# Analogue.net
KiCad netlist of a schematic drawn in Altium Designer
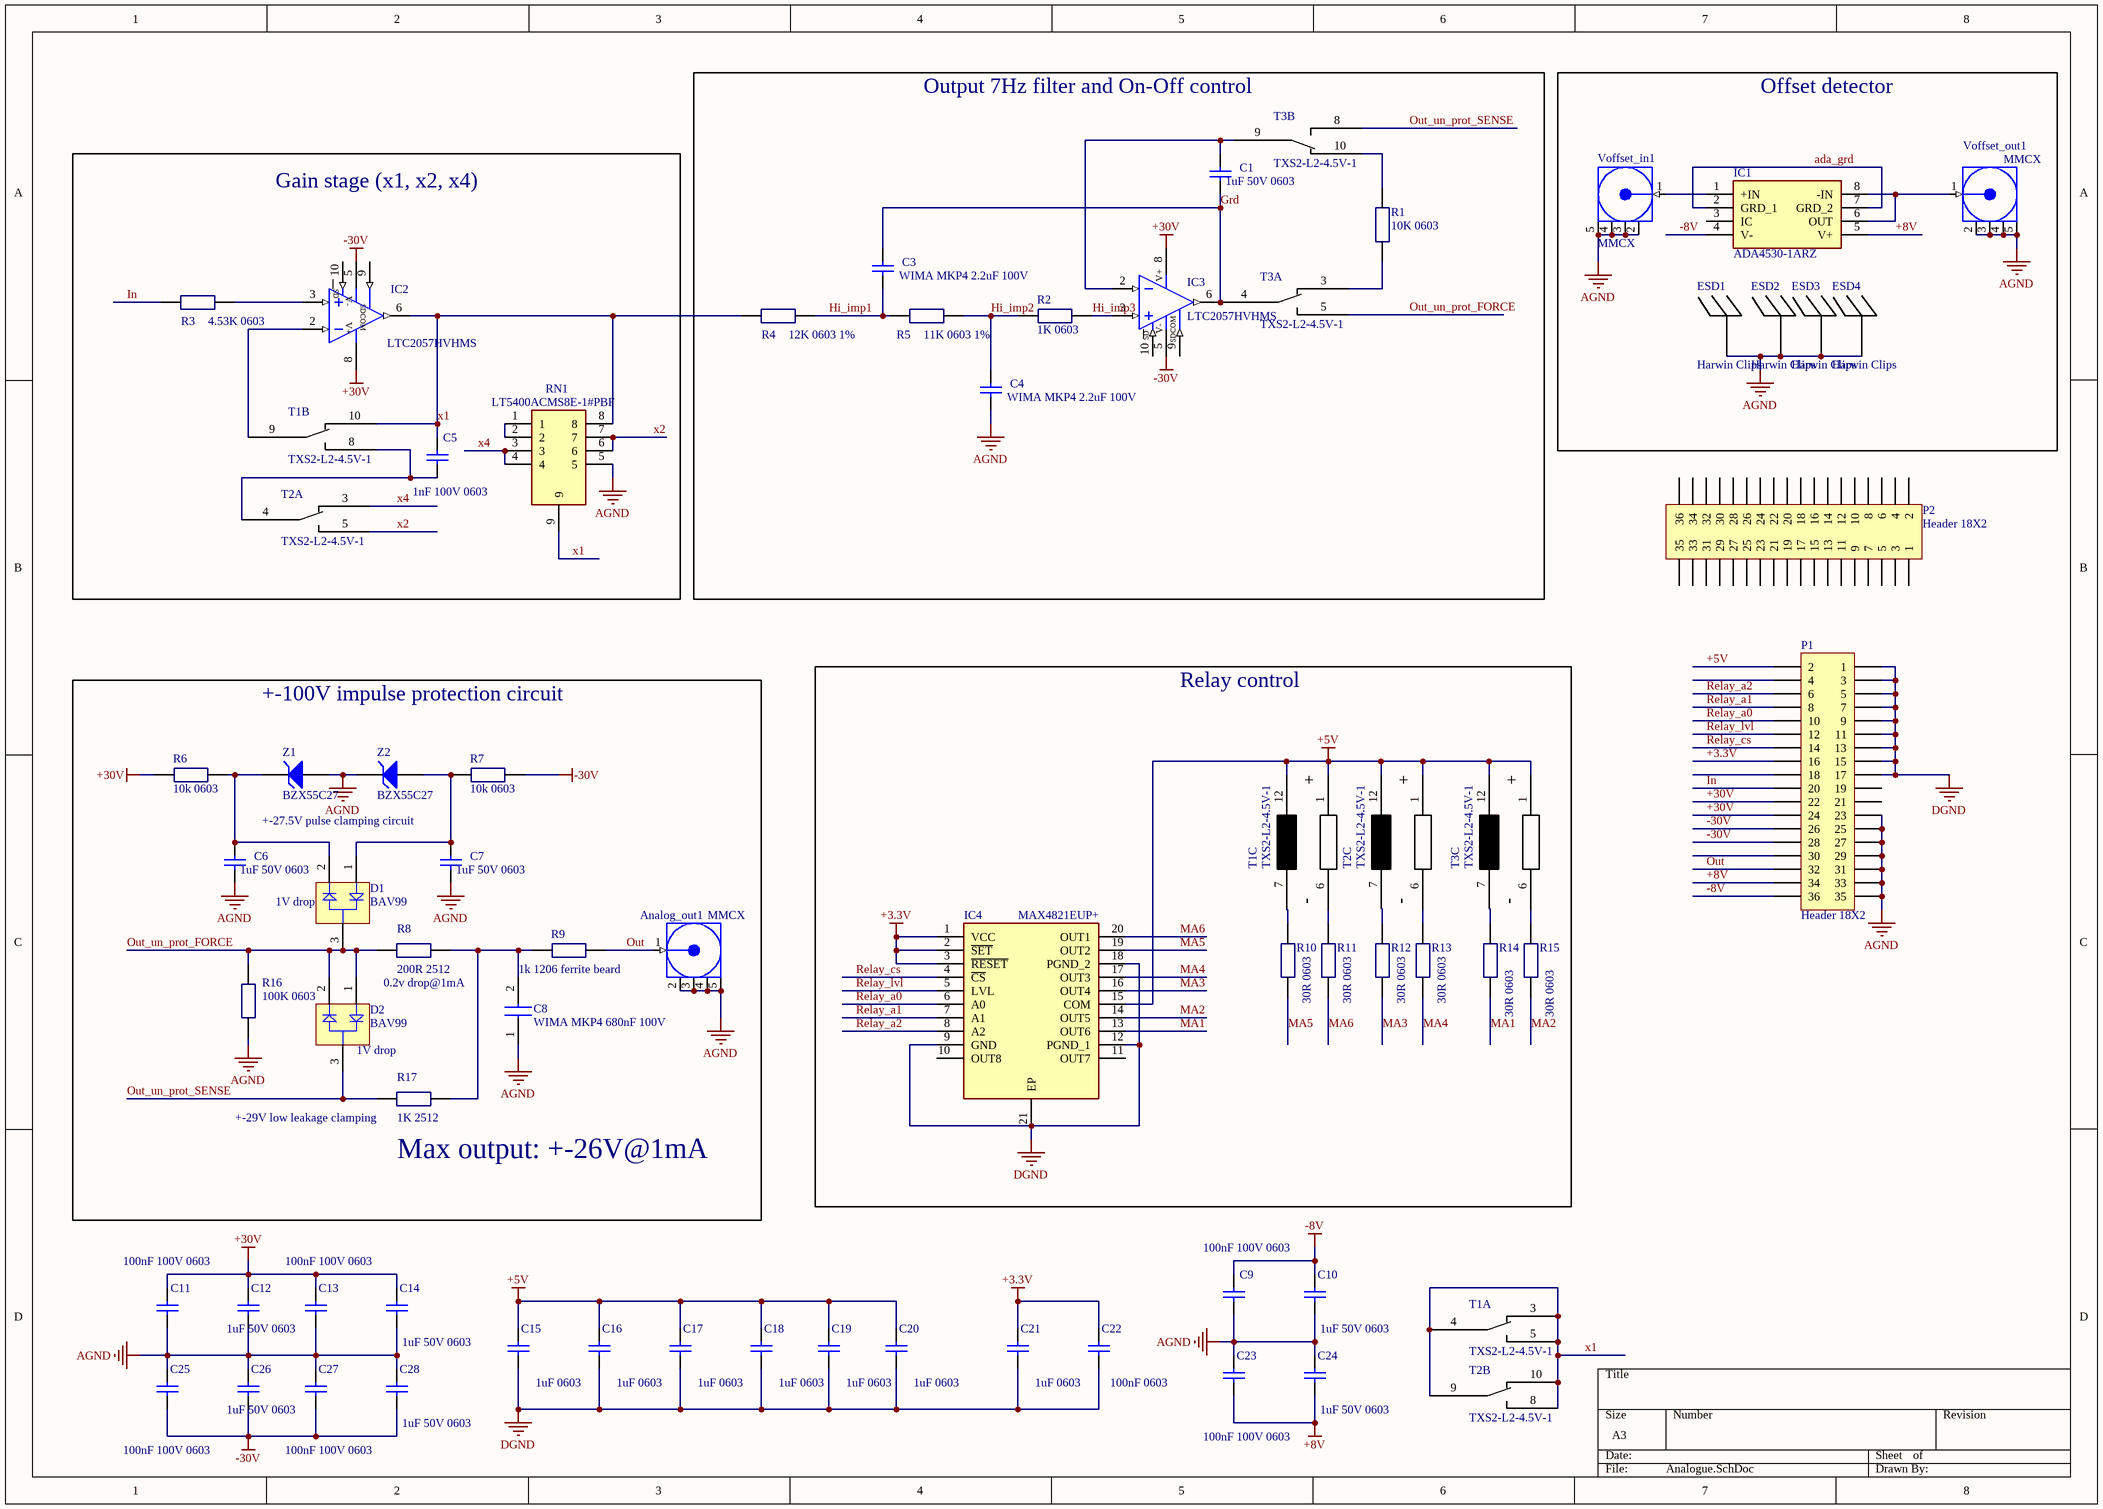
[diagram p0: Analogue.SchDoc]

(export (version "E")
  (design (tool "Eeschema 10.0.6"))
  (components
    (comp (ref "Analog_out1")
      (value "MMCX")
      (footprint "MMCX2.54-V5")
      (description "RF Coaxial PCB Connector, MMCX; Thru-Hole, Vertical Mount Plug,  50 Ohm Impedance")
      (fields (field (name "PUBLISHER") "Altium Limited"))
      (libsource (lib "Miscellaneous Connectors") (part "COAX-M"))
    )
    (comp (ref "C1")
      (value "1uF 50V 0603")
      (footprint "CAP 0603")
      (description "Non-polarised capacitor")
      (fields
        (field (name "PART NUMBER") "CC1206_1UF_25V_10%_X7R")
        (field (name "VOLTAGE") "25V")
        (field (name "AUTHOR") "CERN DEM JLC")
      )
      (libsource (lib "Capacitors") (part "Capacitor - non polarized"))
    )
    (comp (ref "C3")
      (value "WIMA MKP4 2.2uF 100V")
      (footprint "90g WIMA MKP4 2.2uF 100V")
      (description "Non-polarised capacitor")
      (fields
        (field (name "PART NUMBER") "CC1206_1UF_25V_10%_X7R")
        (field (name "VOLTAGE") "25V")
        (field (name "AUTHOR") "CERN DEM JLC")
      )
      (libsource (lib "Capacitors") (part "Capacitor - non polarized"))
    )
    (comp (ref "C4")
      (value "WIMA MKP4 2.2uF 100V")
      (footprint "90g WIMA MKP4 2.2uF 100V")
      (description "Non-polarised capacitor")
      (fields
        (field (name "PART NUMBER") "CC1206_1UF_25V_10%_X7R")
        (field (name "VOLTAGE") "25V")
        (field (name "AUTHOR") "CERN DEM JLC")
      )
      (libsource (lib "Capacitors") (part "Capacitor - non polarized"))
    )
    (comp (ref "C5")
      (value "1nF 100V 0603")
      (footprint "CAP 0603")
      (description "Non-polarised capacitor")
      (fields
        (field (name "PART NUMBER") "CC1206_1UF_25V_10%_X7R")
        (field (name "VOLTAGE") "25V")
        (field (name "AUTHOR") "CERN DEM JLC")
      )
      (libsource (lib "Capacitors") (part "Capacitor - non polarized"))
    )
    (comp (ref "C6")
      (value "1uF 50V 0603")
      (footprint "CAP 0603")
      (description "Non-polarised capacitor")
      (fields
        (field (name "PART NUMBER") "CC1206_1UF_25V_10%_X7R")
        (field (name "VOLTAGE") "25V")
        (field (name "AUTHOR") "CERN DEM JLC")
      )
      (libsource (lib "Capacitors") (part "Capacitor - non polarized"))
    )
    (comp (ref "C7")
      (value "1uF 50V 0603")
      (footprint "CAP 0603")
      (description "Non-polarised capacitor")
      (fields
        (field (name "PART NUMBER") "CC1206_1UF_25V_10%_X7R")
        (field (name "VOLTAGE") "25V")
        (field (name "AUTHOR") "CERN DEM JLC")
      )
      (libsource (lib "Capacitors") (part "Capacitor - non polarized"))
    )
    (comp (ref "C8")
      (value "WIMA MKP4 680nF 100V")
      (footprint "SamacSys:MKP4F036804F00KSSD")
      (description "Capacitor")
      (fields
        (field (name "MANUFACTURER_PART_NUMBER") "MKP4F036804F00KSSD")
        (field (name "MOUSER PART NUMBER") "505-MKP4F036804F00KS")
      )
      (libsource (lib "SamacSys") (part "MKP4F036804F00KSSD"))
    )
    (comp (ref "C9")
      (value "100nF 100V 0603")
      (footprint "CAP 0603")
      (description "Non-polarised capacitor")
      (fields
        (field (name "PART NUMBER") "CC1206_1UF_25V_10%_X7R")
        (field (name "VOLTAGE") "25V")
        (field (name "AUTHOR") "CERN DEM JLC")
      )
      (libsource (lib "Capacitors") (part "Capacitor - non polarized"))
    )
    (comp (ref "C10")
      (value "1uF 50V 0603")
      (footprint "CAP 0603")
      (description "Non-polarised capacitor")
      (fields
        (field (name "PART NUMBER") "CC1206_1UF_25V_10%_X7R")
        (field (name "VOLTAGE") "25V")
        (field (name "AUTHOR") "CERN DEM JLC")
      )
      (libsource (lib "Capacitors") (part "Capacitor - non polarized"))
    )
    (comp (ref "C11")
      (value "100nF 100V 0603")
      (footprint "CAP 0603")
      (description "Non-polarised capacitor")
      (fields
        (field (name "PART NUMBER") "CC1206_1UF_25V_10%_X7R")
        (field (name "VOLTAGE") "25V")
        (field (name "AUTHOR") "CERN DEM JLC")
      )
      (libsource (lib "Capacitors") (part "Capacitor - non polarized"))
    )
    (comp (ref "C12")
      (value "1uF 50V 0603")
      (footprint "CAP 0603")
      (description "Non-polarised capacitor")
      (fields
        (field (name "PART NUMBER") "CC1206_1UF_25V_10%_X7R")
        (field (name "VOLTAGE") "25V")
        (field (name "AUTHOR") "CERN DEM JLC")
      )
      (libsource (lib "Capacitors") (part "Capacitor - non polarized"))
    )
    (comp (ref "C13")
      (value "100nF 100V 0603")
      (footprint "CAP 0603")
      (description "Non-polarised capacitor")
      (fields
        (field (name "PART NUMBER") "CC1206_1UF_25V_10%_X7R")
        (field (name "VOLTAGE") "25V")
        (field (name "AUTHOR") "CERN DEM JLC")
      )
      (libsource (lib "Capacitors") (part "Capacitor - non polarized"))
    )
    (comp (ref "C14")
      (value "1uF 50V 0603")
      (footprint "CAP 0603")
      (description "Non-polarised capacitor")
      (fields
        (field (name "PART NUMBER") "CC1206_1UF_25V_10%_X7R")
        (field (name "VOLTAGE") "25V")
        (field (name "AUTHOR") "CERN DEM JLC")
      )
      (libsource (lib "Capacitors") (part "Capacitor - non polarized"))
    )
    (comp (ref "C15")
      (value "1uF 0603")
      (footprint "CAP 0603")
      (description "Non-polarised capacitor")
      (fields
        (field (name "PART NUMBER") "CC1206_1UF_25V_10%_X7R")
        (field (name "VOLTAGE") "25V")
        (field (name "AUTHOR") "CERN DEM JLC")
      )
      (libsource (lib "Capacitors") (part "Capacitor - non polarized"))
    )
    (comp (ref "C16")
      (value "1uF 0603")
      (footprint "CAP 0603")
      (description "Non-polarised capacitor")
      (fields
        (field (name "PART NUMBER") "CC1206_1UF_25V_10%_X7R")
        (field (name "VOLTAGE") "25V")
        (field (name "AUTHOR") "CERN DEM JLC")
      )
      (libsource (lib "Capacitors") (part "Capacitor - non polarized"))
    )
    (comp (ref "C17")
      (value "1uF 0603")
      (footprint "CAP 0603")
      (description "Non-polarised capacitor")
      (fields
        (field (name "PART NUMBER") "CC1206_1UF_25V_10%_X7R")
        (field (name "VOLTAGE") "25V")
        (field (name "AUTHOR") "CERN DEM JLC")
      )
      (libsource (lib "Capacitors") (part "Capacitor - non polarized"))
    )
    (comp (ref "C18")
      (value "1uF 0603")
      (footprint "CAP 0603")
      (description "Non-polarised capacitor")
      (fields
        (field (name "PART NUMBER") "CC1206_1UF_25V_10%_X7R")
        (field (name "VOLTAGE") "25V")
        (field (name "AUTHOR") "CERN DEM JLC")
      )
      (libsource (lib "Capacitors") (part "Capacitor - non polarized"))
    )
    (comp (ref "C19")
      (value "1uF 0603")
      (footprint "CAP 0603")
      (description "Non-polarised capacitor")
      (fields
        (field (name "PART NUMBER") "CC1206_1UF_25V_10%_X7R")
        (field (name "VOLTAGE") "25V")
        (field (name "AUTHOR") "CERN DEM JLC")
      )
      (libsource (lib "Capacitors") (part "Capacitor - non polarized"))
    )
    (comp (ref "C20")
      (value "1uF 0603")
      (footprint "CAP 0603")
      (description "Non-polarised capacitor")
      (fields
        (field (name "PART NUMBER") "CC1206_1UF_25V_10%_X7R")
        (field (name "VOLTAGE") "25V")
        (field (name "AUTHOR") "CERN DEM JLC")
      )
      (libsource (lib "Capacitors") (part "Capacitor - non polarized"))
    )
    (comp (ref "C21")
      (value "1uF 0603")
      (footprint "CAP 0603")
      (description "Non-polarised capacitor")
      (fields
        (field (name "PART NUMBER") "CC1206_1UF_25V_10%_X7R")
        (field (name "VOLTAGE") "25V")
        (field (name "AUTHOR") "CERN DEM JLC")
      )
      (libsource (lib "Capacitors") (part "Capacitor - non polarized"))
    )
    (comp (ref "C22")
      (value "100nF 0603")
      (footprint "CAP 0603")
      (description "Non-polarised capacitor")
      (fields
        (field (name "PART NUMBER") "CC1206_1UF_25V_10%_X7R")
        (field (name "VOLTAGE") "25V")
        (field (name "AUTHOR") "CERN DEM JLC")
      )
      (libsource (lib "Capacitors") (part "Capacitor - non polarized"))
    )
    (comp (ref "C23")
      (value "100nF 100V 0603")
      (footprint "CAP 0603")
      (description "Non-polarised capacitor")
      (fields
        (field (name "PART NUMBER") "CC1206_1UF_25V_10%_X7R")
        (field (name "VOLTAGE") "25V")
        (field (name "AUTHOR") "CERN DEM JLC")
      )
      (libsource (lib "Capacitors") (part "Capacitor - non polarized"))
    )
    (comp (ref "C24")
      (value "1uF 50V 0603")
      (footprint "CAP 0603")
      (description "Non-polarised capacitor")
      (fields
        (field (name "PART NUMBER") "CC1206_1UF_25V_10%_X7R")
        (field (name "VOLTAGE") "25V")
        (field (name "AUTHOR") "CERN DEM JLC")
      )
      (libsource (lib "Capacitors") (part "Capacitor - non polarized"))
    )
    (comp (ref "C25")
      (value "100nF 100V 0603")
      (footprint "CAP 0603")
      (description "Non-polarised capacitor")
      (fields
        (field (name "PART NUMBER") "CC1206_1UF_25V_10%_X7R")
        (field (name "VOLTAGE") "25V")
        (field (name "AUTHOR") "CERN DEM JLC")
      )
      (libsource (lib "Capacitors") (part "Capacitor - non polarized"))
    )
    (comp (ref "C26")
      (value "1uF 50V 0603")
      (footprint "CAP 0603")
      (description "Non-polarised capacitor")
      (fields
        (field (name "PART NUMBER") "CC1206_1UF_25V_10%_X7R")
        (field (name "VOLTAGE") "25V")
        (field (name "AUTHOR") "CERN DEM JLC")
      )
      (libsource (lib "Capacitors") (part "Capacitor - non polarized"))
    )
    (comp (ref "C27")
      (value "100nF 100V 0603")
      (footprint "CAP 0603")
      (description "Non-polarised capacitor")
      (fields
        (field (name "PART NUMBER") "CC1206_1UF_25V_10%_X7R")
        (field (name "VOLTAGE") "25V")
        (field (name "AUTHOR") "CERN DEM JLC")
      )
      (libsource (lib "Capacitors") (part "Capacitor - non polarized"))
    )
    (comp (ref "C28")
      (value "1uF 50V 0603")
      (footprint "CAP 0603")
      (description "Non-polarised capacitor")
      (fields
        (field (name "PART NUMBER") "CC1206_1UF_25V_10%_X7R")
        (field (name "VOLTAGE") "25V")
        (field (name "AUTHOR") "CERN DEM JLC")
      )
      (libsource (lib "Capacitors") (part "Capacitor - non polarized"))
    )
    (comp (ref "D1")
      (value "BAV99")
      (footprint "INF-SOT23_N")
      (description "Silicon Switching Diode, SOT23, Reel, Green")
      (fields (field (name "MANUFACTURER") "Infineon"))
      (libsource (lib "Infineon_Transistor_&_Diode") (part "BAV99"))
    )
    (comp (ref "D2")
      (value "BAV99")
      (footprint "INF-SOT23_N")
      (description "Silicon Switching Diode, SOT23, Reel, Green")
      (fields (field (name "MANUFACTURER") "Infineon"))
      (libsource (lib "Infineon_Transistor_&_Diode") (part "BAV99"))
    )
    (comp (ref "ESD1")
      (value "Harwin Clips")
      (footprint "HARWIN - S0981-46R - CLIP")
      (libsource (lib "My SCH library") (part "Harwin Clips"))
    )
    (comp (ref "ESD2")
      (value "Harwin Clips")
      (footprint "HARWIN - S0981-46R - CLIP")
      (libsource (lib "My SCH library") (part "Harwin Clips"))
    )
    (comp (ref "ESD3")
      (value "Harwin Clips")
      (footprint "HARWIN - S0981-46R - CLIP")
      (libsource (lib "My SCH library") (part "Harwin Clips"))
    )
    (comp (ref "ESD4")
      (value "Harwin Clips")
      (footprint "HARWIN - S0981-46R - CLIP")
      (libsource (lib "My SCH library") (part "Harwin Clips"))
    )
    (comp (ref "IC1")
      (value "ADA4530-1ARZ")
      (footprint "SamacSys:SOIC127P600X175-8N")
      (description "Integrated Circuit")
      (fields (field (name "MOUSER PART NUMBER") "584-ADA4530-1ARZ"))
      (libsource (lib "*") (part "ADA4530-1ARZ"))
    )
    (comp (ref "IC2")
      (value "LTC2057HVHMS")
      (footprint "LT-MS-10_M")
      (description "High Voltage, Low Noise, Zero-Drift Operational  Amplifier")
      (libsource (lib "Operational Amplifiers") (part "LTC2057xHMS"))
    )
    (comp (ref "IC3")
      (value "LTC2057HVHMS")
      (footprint "LT-MS-10_M")
      (description "High Voltage, Low Noise, Zero-Drift Operational  Amplifier")
      (libsource (lib "Operational Amplifiers") (part "LTC2057xHMS"))
    )
    (comp (ref "IC4")
      (value "MAX4821EUP+")
      (footprint "SamacSys:SOP65P638X110-21N")
      (description "Integrated Circuit")
      (fields (field (name "MOUSER PART NUMBER") "700-MAX4821EUP"))
      (libsource (lib "*") (part "MAX4821EUP+"))
    )
    (comp (ref "P1")
      (value "Header 18X2")
      (footprint "HDR2X18")
      (description "Header, 18-Pin, Dual row")
      (fields (field (name "PUBLISHER") "Altium Limited"))
      (libsource (lib "") (part "Header 18X2_1"))
    )
    (comp (ref "P2")
      (value "Header 18X2")
      (footprint "HDR2X18")
      (description "Header, 18-Pin, Dual row")
      (fields (field (name "PUBLISHER") "Altium Limited"))
      (libsource (lib "Miscellaneous Connectors") (part "Header 18X2"))
    )
    (comp (ref "R1")
      (value "10K 0603")
      (footprint "1608[0603]")
      (libsource (lib "Микрон-3") (part "Resistor 0805"))
    )
    (comp (ref "R2")
      (value "1K 0603")
      (footprint "1608[0603]")
      (libsource (lib "Микрон-3") (part "Resistor 0805"))
    )
    (comp (ref "R3")
      (value "4.53K 0603")
      (footprint "1608[0603]")
      (libsource (lib "Микрон-3") (part "Resistor 0805"))
    )
    (comp (ref "R4")
      (value "12K 0603 1%")
      (footprint "1608[0603]")
      (libsource (lib "Микрон-3") (part "Resistor 0805"))
    )
    (comp (ref "R5")
      (value "11K 0603 1%")
      (footprint "1608[0603]")
      (libsource (lib "Микрон-3") (part "Resistor 0805"))
    )
    (comp (ref "R6")
      (value "10k 0603")
      (footprint "1608[0603]")
      (libsource (lib "Микрон-3") (part "Resistor 0805"))
    )
    (comp (ref "R7")
      (value "10k 0603")
      (footprint "1608[0603]")
      (libsource (lib "Микрон-3") (part "Resistor 0805"))
    )
    (comp (ref "R8")
      (value "200R 2512")
      (footprint "CRCW2512")
      (libsource (lib "Микрон-3") (part "Resistor 0805"))
    )
    (comp (ref "R9")
      (value "1k 1206 ferrite beard")
      (footprint "Yageo HV 1206")
      (libsource (lib "Микрон-3") (part "Resistor 0805"))
    )
    (comp (ref "R10")
      (value "30R 0603")
      (footprint "1608[0603]")
      (libsource (lib "Микрон-3") (part "Resistor 0805"))
    )
    (comp (ref "R11")
      (value "30R 0603")
      (footprint "1608[0603]")
      (libsource (lib "Микрон-3") (part "Resistor 0805"))
    )
    (comp (ref "R12")
      (value "30R 0603")
      (footprint "1608[0603]")
      (libsource (lib "Микрон-3") (part "Resistor 0805"))
    )
    (comp (ref "R13")
      (value "30R 0603")
      (footprint "1608[0603]")
      (libsource (lib "Микрон-3") (part "Resistor 0805"))
    )
    (comp (ref "R14")
      (value "30R 0603")
      (footprint "1608[0603]")
      (libsource (lib "Микрон-3") (part "Resistor 0805"))
    )
    (comp (ref "R15")
      (value "30R 0603")
      (footprint "1608[0603]")
      (libsource (lib "Микрон-3") (part "Resistor 0805"))
    )
    (comp (ref "R16")
      (value "100K 0603")
      (footprint "1608[0603]_RES")
      (libsource (lib "Микрон-3") (part "Resistor 0805"))
    )
    (comp (ref "R17")
      (value "1K 2512")
      (footprint "CRCW2512")
      (libsource (lib "Микрон-3") (part "Resistor 0805"))
    )
    (comp (ref "RN1")
      (value "LT5400ACMS8E-1#PBF")
      (footprint "SamacSys:SOP65P490X110-9N")
      (description "Resistor Network")
      (fields (field (name "MOUSER PART NUMBER") "584-5400ACMS8E-1PBF"))
      (libsource (lib "*") (part "LT5400ACMS8E-1#PBF"))
    )
    (comp (ref "T1")
      (value "TXS2-L2-4.5V-1")
      (footprint "TXS2-L2-4.5V-1")
      (libsource (lib "") (part "TXS2-L2-4.5V-1_2"))
    )
    (comp (ref "T2")
      (value "TXS2-L2-4.5V-1")
      (footprint "TXS2-L2-4.5V-1")
      (libsource (lib "") (part "TXS2-L2-4.5V-1_2"))
    )
    (comp (ref "T3")
      (value "TXS2-L2-4.5V-1")
      (footprint "TXS2-L2-4.5V-1")
      (libsource (lib "My SCH library") (part "TXS2-L2-4.5V-1"))
    )
    (comp (ref "Voffset_in1")
      (value "MMCX")
      (footprint "MMCX2.54-V5")
      (description "RF Coaxial PCB Connector, MMCX; Thru-Hole, Vertical Mount Plug,  50 Ohm Impedance")
      (fields (field (name "PUBLISHER") "Altium Limited"))
      (libsource (lib "Miscellaneous Connectors") (part "COAX-M"))
    )
    (comp (ref "Voffset_out1")
      (value "MMCX")
      (footprint "MMCX2.54-V5")
      (description "RF Coaxial PCB Connector, MMCX; Thru-Hole, Vertical Mount Plug,  50 Ohm Impedance")
      (fields (field (name "PUBLISHER") "Altium Limited"))
      (libsource (lib "Miscellaneous Connectors") (part "COAX-M"))
    )
    (comp (ref "Z1")
      (value "BZX55C27")
      (footprint "DO-35")
      (description "Silicon Epitaxial Planar Zener Diode (0.3 to 0.5W)")
      (fields (field (name "PUBLISHER") "Altium Limited"))
      (libsource (lib "Vishay Telefunken Discrete Diode") (part "BZX55C27"))
    )
    (comp (ref "Z2")
      (value "BZX55C27")
      (footprint "DO-35")
      (description "Silicon Epitaxial Planar Zener Diode (0.3 to 0.5W)")
      (fields (field (name "PUBLISHER") "Altium Limited"))
      (libsource (lib "Vishay Telefunken Discrete Diode") (part "BZX55C27"))
    )
  )
  (nets
    (net (code "1") (name "+3.3V") (class "Default")
      (node (ref "C21") (pin "1") (pinfunction "1_1") (pintype "passive"))
      (node (ref "C22") (pin "1") (pinfunction "1_1") (pintype "passive"))
      (node (ref "IC4") (pin "1") (pinfunction "VCC_1") (pintype "passive"))
      (node (ref "IC4") (pin "2") (pinfunction "~{SET}_2") (pintype "passive"))
      (node (ref "IC4") (pin "3") (pinfunction "~{RESET}_3") (pintype "passive"))
      (node (ref "P1") (pin "16") (pinfunction "16_16") (pintype "passive"))
    )
    (net (code "2") (name "+5V") (class "Default")
      (node (ref "C15") (pin "1") (pinfunction "1_1") (pintype "passive"))
      (node (ref "C16") (pin "1") (pinfunction "1_1") (pintype "passive"))
      (node (ref "C17") (pin "1") (pinfunction "1_1") (pintype "passive"))
      (node (ref "C18") (pin "1") (pinfunction "1_1") (pintype "passive"))
      (node (ref "C19") (pin "1") (pinfunction "1_1") (pintype "passive"))
      (node (ref "C20") (pin "1") (pinfunction "1_1") (pintype "passive"))
      (node (ref "IC4") (pin "15") (pinfunction "COM_15") (pintype "passive"))
      (node (ref "P1") (pin "2") (pinfunction "2_2") (pintype "passive"))
      (node (ref "T1") (pin "1") (pinfunction "1_1") (pintype "passive"))
      (node (ref "T1") (pin "12") (pinfunction "12_12") (pintype "passive"))
      (node (ref "T2") (pin "1") (pinfunction "1_1") (pintype "passive"))
      (node (ref "T2") (pin "12") (pinfunction "12_12") (pintype "passive"))
      (node (ref "T3") (pin "1") (pinfunction "1_1") (pintype "passive"))
      (node (ref "T3") (pin "12") (pinfunction "12_12") (pintype "passive"))
    )
    (net (code "3") (name "+8V") (class "Default")
      (node (ref "C23") (pin "2") (pinfunction "2_2") (pintype "passive"))
      (node (ref "C24") (pin "2") (pinfunction "2_2") (pintype "passive"))
      (node (ref "IC1") (pin "5") (pinfunction "V+_5") (pintype "passive"))
      (node (ref "P1") (pin "34") (pinfunction "34_34") (pintype "passive"))
    )
    (net (code "4") (name "+30V") (class "Default")
      (node (ref "C11") (pin "1") (pinfunction "1_1") (pintype "passive"))
      (node (ref "C12") (pin "1") (pinfunction "1_1") (pintype "passive"))
      (node (ref "C13") (pin "1") (pinfunction "1_1") (pintype "passive"))
      (node (ref "C14") (pin "1") (pinfunction "1_1") (pintype "passive"))
      (node (ref "IC2") (pin "8") (pinfunction "V+_8") (pintype "power_in"))
      (node (ref "IC3") (pin "8") (pinfunction "V+_8") (pintype "power_in"))
      (node (ref "P1") (pin "22") (pinfunction "22_22") (pintype "passive"))
      (node (ref "P1") (pin "24") (pinfunction "24_24") (pintype "passive"))
      (node (ref "R6") (pin "1") (pinfunction "A_1") (pintype "passive"))
    )
    (net (code "5") (name "-8V") (class "Default")
      (node (ref "C10") (pin "1") (pinfunction "1_1") (pintype "passive"))
      (node (ref "C9") (pin "1") (pinfunction "1_1") (pintype "passive"))
      (node (ref "IC1") (pin "4") (pinfunction "V-_4") (pintype "passive"))
      (node (ref "P1") (pin "36") (pinfunction "36_36") (pintype "passive"))
    )
    (net (code "6") (name "-30V") (class "Default")
      (node (ref "C25") (pin "2") (pinfunction "2_2") (pintype "passive"))
      (node (ref "C26") (pin "2") (pinfunction "2_2") (pintype "passive"))
      (node (ref "C27") (pin "2") (pinfunction "2_2") (pintype "passive"))
      (node (ref "C28") (pin "2") (pinfunction "2_2") (pintype "passive"))
      (node (ref "IC2") (pin "5") (pinfunction "V-_5") (pintype "power_in"))
      (node (ref "IC3") (pin "5") (pinfunction "V-_5") (pintype "power_in"))
      (node (ref "P1") (pin "26") (pinfunction "26_26") (pintype "passive"))
      (node (ref "P1") (pin "28") (pinfunction "28_28") (pintype "passive"))
      (node (ref "R7") (pin "2") (pinfunction "2_2") (pintype "passive"))
    )
    (net (code "7") (name "/Grd") (class "Default")
      (node (ref "C1") (pin "2") (pinfunction "2_2") (pintype "passive"))
      (node (ref "C3") (pin "1") (pinfunction "1_1") (pintype "passive"))
      (node (ref "IC3") (pin "6") (pinfunction "OUT_6") (pintype "output"))
      (node (ref "T3") (pin "4") (pinfunction "4_4") (pintype "passive"))
    )
    (net (code "8") (name "/Hi_imp1") (class "Default")
      (node (ref "C3") (pin "2") (pinfunction "2_2") (pintype "passive"))
      (node (ref "R4") (pin "1") (pinfunction "A_1") (pintype "passive"))
      (node (ref "R5") (pin "2") (pinfunction "2_2") (pintype "passive"))
    )
    (net (code "9") (name "/Hi_imp2") (class "Default")
      (node (ref "C4") (pin "1") (pinfunction "1_1") (pintype "passive"))
      (node (ref "R2") (pin "1") (pinfunction "A_1") (pintype "passive"))
      (node (ref "R5") (pin "1") (pinfunction "A_1") (pintype "passive"))
    )
    (net (code "10") (name "/Hi_imp3") (class "Default")
      (node (ref "IC3") (pin "3") (pinfunction "IN+_3") (pintype "input"))
      (node (ref "R2") (pin "2") (pinfunction "2_2") (pintype "passive"))
    )
    (net (code "11") (name "/In") (class "Default")
      (node (ref "P1") (pin "20") (pinfunction "20_20") (pintype "passive"))
      (node (ref "R3") (pin "2") (pinfunction "2_2") (pintype "passive"))
    )
    (net (code "12") (name "/MA1") (class "Default")
      (node (ref "IC4") (pin "13") (pinfunction "OUT6_13") (pintype "passive"))
      (node (ref "R14") (pin "2") (pinfunction "2_2") (pintype "passive"))
    )
    (net (code "13") (name "/MA2") (class "Default")
      (node (ref "IC4") (pin "14") (pinfunction "OUT5_14") (pintype "passive"))
      (node (ref "R15") (pin "2") (pinfunction "2_2") (pintype "passive"))
    )
    (net (code "14") (name "/MA3") (class "Default")
      (node (ref "IC4") (pin "16") (pinfunction "OUT4_16") (pintype "passive"))
      (node (ref "R12") (pin "2") (pinfunction "2_2") (pintype "passive"))
    )
    (net (code "15") (name "/MA4") (class "Default")
      (node (ref "IC4") (pin "17") (pinfunction "OUT3_17") (pintype "passive"))
      (node (ref "R13") (pin "2") (pinfunction "2_2") (pintype "passive"))
    )
    (net (code "16") (name "/MA5") (class "Default")
      (node (ref "IC4") (pin "19") (pinfunction "OUT2_19") (pintype "passive"))
      (node (ref "R10") (pin "2") (pinfunction "2_2") (pintype "passive"))
    )
    (net (code "17") (name "/MA6") (class "Default")
      (node (ref "IC4") (pin "20") (pinfunction "OUT1_20") (pintype "passive"))
      (node (ref "R11") (pin "2") (pinfunction "2_2") (pintype "passive"))
    )
    (net (code "18") (name "/Out") (class "Default")
      (node (ref "Analog_out1") (pin "1") (pinfunction "Signal_1") (pintype "input"))
      (node (ref "P1") (pin "32") (pinfunction "32_32") (pintype "passive"))
      (node (ref "R9") (pin "2") (pinfunction "2_2") (pintype "passive"))
    )
    (net (code "19") (name "/Out_un_prot_FORCE") (class "Default")
      (node (ref "D1") (pin "3") (pinfunction "C_3") (pintype "passive"))
      (node (ref "D2") (pin "1") (pinfunction "A1_1") (pintype "passive"))
      (node (ref "D2") (pin "2") (pinfunction "K2_2") (pintype "passive"))
      (node (ref "R16") (pin "1") (pinfunction "A_1") (pintype "passive"))
      (node (ref "R8") (pin "2") (pinfunction "2_2") (pintype "passive"))
      (node (ref "T3") (pin "5") (pinfunction "5_5") (pintype "passive"))
    )
    (net (code "20") (name "/Out_un_prot_SENSE") (class "Default")
      (node (ref "D2") (pin "3") (pinfunction "C_3") (pintype "passive"))
      (node (ref "R17") (pin "2") (pinfunction "2_2") (pintype "passive"))
      (node (ref "T3") (pin "8") (pinfunction "8_8") (pintype "passive"))
    )
    (net (code "21") (name "/Relay_a0") (class "Default")
      (node (ref "IC4") (pin "6") (pinfunction "A0_6") (pintype "passive"))
      (node (ref "P1") (pin "10") (pinfunction "10_10") (pintype "passive"))
    )
    (net (code "22") (name "/Relay_a1") (class "Default")
      (node (ref "IC4") (pin "7") (pinfunction "A1_7") (pintype "passive"))
      (node (ref "P1") (pin "8") (pinfunction "8_8") (pintype "passive"))
    )
    (net (code "23") (name "/Relay_a2") (class "Default")
      (node (ref "IC4") (pin "8") (pinfunction "A2_8") (pintype "passive"))
      (node (ref "P1") (pin "6") (pinfunction "6_6") (pintype "passive"))
    )
    (net (code "24") (name "/Relay_cs") (class "Default")
      (node (ref "IC4") (pin "4") (pinfunction "~{CS}_4") (pintype "passive"))
      (node (ref "P1") (pin "14") (pinfunction "14_14") (pintype "passive"))
    )
    (net (code "25") (name "/Relay_lvl") (class "Default")
      (node (ref "IC4") (pin "5") (pinfunction "LVL_5") (pintype "passive"))
      (node (ref "P1") (pin "12") (pinfunction "12_12") (pintype "passive"))
    )
    (net (code "26") (name "/ada_grd") (class "Default")
      (node (ref "IC1") (pin "2") (pinfunction "GRD_1_2") (pintype "passive"))
      (node (ref "IC1") (pin "7") (pinfunction "GRD_2_7") (pintype "passive"))
    )
    (net (code "27") (name "/x1") (class "Default")
      (node (ref "C5") (pin "1") (pinfunction "1_1") (pintype "passive"))
      (node (ref "IC2") (pin "6") (pinfunction "OUT_6") (pintype "output"))
      (node (ref "R4") (pin "2") (pinfunction "2_2") (pintype "passive"))
      (node (ref "RN1") (pin "8") (pinfunction "8_8") (pintype "passive"))
      (node (ref "RN1") (pin "9") (pinfunction "9_9") (pintype "passive"))
      (node (ref "T1") (pin "10") (pinfunction "10_10") (pintype "passive"))
      (node (ref "T1") (pin "3") (pinfunction "3_3") (pintype "passive"))
      (node (ref "T1") (pin "4") (pinfunction "4_4") (pintype "passive"))
      (node (ref "T1") (pin "5") (pinfunction "5_5") (pintype "passive"))
      (node (ref "T2") (pin "10") (pinfunction "10_10") (pintype "passive"))
      (node (ref "T2") (pin "8") (pinfunction "8_8") (pintype "passive"))
      (node (ref "T2") (pin "9") (pinfunction "9_9") (pintype "passive"))
    )
    (net (code "28") (name "/x2") (class "Default")
      (node (ref "RN1") (pin "6") (pinfunction "6_6") (pintype "passive"))
      (node (ref "RN1") (pin "7") (pinfunction "7_7") (pintype "passive"))
      (node (ref "T2") (pin "5") (pinfunction "5_5") (pintype "passive"))
    )
    (net (code "29") (name "/x4") (class "Default")
      (node (ref "RN1") (pin "3") (pinfunction "3_3") (pintype "passive"))
      (node (ref "RN1") (pin "4") (pinfunction "4_4") (pintype "passive"))
      (node (ref "T2") (pin "3") (pinfunction "3_3") (pintype "passive"))
    )
    (net (code "30") (name "AGND") (class "Default")
      (node (ref "Analog_out1") (pin "2") (pinfunction "GND_2") (pintype "power_in"))
      (node (ref "Analog_out1") (pin "3") (pinfunction "GND_3") (pintype "power_in"))
      (node (ref "Analog_out1") (pin "4") (pinfunction "GND_4") (pintype "power_in"))
      (node (ref "Analog_out1") (pin "5") (pinfunction "GND_5") (pintype "power_in"))
      (node (ref "C10") (pin "2") (pinfunction "2_2") (pintype "passive"))
      (node (ref "C11") (pin "2") (pinfunction "2_2") (pintype "passive"))
      (node (ref "C12") (pin "2") (pinfunction "2_2") (pintype "passive"))
      (node (ref "C13") (pin "2") (pinfunction "2_2") (pintype "passive"))
      (node (ref "C14") (pin "2") (pinfunction "2_2") (pintype "passive"))
      (node (ref "C23") (pin "1") (pinfunction "1_1") (pintype "passive"))
      (node (ref "C24") (pin "1") (pinfunction "1_1") (pintype "passive"))
      (node (ref "C25") (pin "1") (pinfunction "1_1") (pintype "passive"))
      (node (ref "C26") (pin "1") (pinfunction "1_1") (pintype "passive"))
      (node (ref "C27") (pin "1") (pinfunction "1_1") (pintype "passive"))
      (node (ref "C28") (pin "1") (pinfunction "1_1") (pintype "passive"))
      (node (ref "C4") (pin "2") (pinfunction "2_2") (pintype "passive"))
      (node (ref "C6") (pin "2") (pinfunction "2_2") (pintype "passive"))
      (node (ref "C7") (pin "2") (pinfunction "2_2") (pintype "passive"))
      (node (ref "C8") (pin "1") (pinfunction "1_1") (pintype "passive"))
      (node (ref "C9") (pin "2") (pinfunction "2_2") (pintype "passive"))
      (node (ref "ESD1") (pin "1") (pinfunction "1_1") (pintype "passive"))
      (node (ref "ESD2") (pin "1") (pinfunction "1_1") (pintype "passive"))
      (node (ref "ESD3") (pin "1") (pinfunction "1_1") (pintype "passive"))
      (node (ref "ESD4") (pin "1") (pinfunction "1_1") (pintype "passive"))
      (node (ref "P1") (pin "23") (pinfunction "23_23") (pintype "passive"))
      (node (ref "P1") (pin "25") (pinfunction "25_25") (pintype "passive"))
      (node (ref "P1") (pin "27") (pinfunction "27_27") (pintype "passive"))
      (node (ref "P1") (pin "29") (pinfunction "29_29") (pintype "passive"))
      (node (ref "P1") (pin "31") (pinfunction "31_31") (pintype "passive"))
      (node (ref "P1") (pin "33") (pinfunction "33_33") (pintype "passive"))
      (node (ref "P1") (pin "35") (pinfunction "35_35") (pintype "passive"))
      (node (ref "R16") (pin "2") (pinfunction "2_2") (pintype "passive"))
      (node (ref "RN1") (pin "5") (pinfunction "5_5") (pintype "passive"))
      (node (ref "Voffset_in1") (pin "2") (pinfunction "GND_2") (pintype "power_in"))
      (node (ref "Voffset_in1") (pin "3") (pinfunction "GND_3") (pintype "power_in"))
      (node (ref "Voffset_in1") (pin "4") (pinfunction "GND_4") (pintype "power_in"))
      (node (ref "Voffset_in1") (pin "5") (pinfunction "GND_5") (pintype "power_in"))
      (node (ref "Voffset_out1") (pin "2") (pinfunction "GND_2") (pintype "power_in"))
      (node (ref "Voffset_out1") (pin "3") (pinfunction "GND_3") (pintype "power_in"))
      (node (ref "Voffset_out1") (pin "4") (pinfunction "GND_4") (pintype "power_in"))
      (node (ref "Voffset_out1") (pin "5") (pinfunction "GND_5") (pintype "power_in"))
      (node (ref "Z1") (pin "1") (pinfunction "A_1") (pintype "passive"))
      (node (ref "Z2") (pin "2") (pinfunction "K_2") (pintype "passive"))
    )
    (net (code "31") (name "DGND") (class "Default")
      (node (ref "C15") (pin "2") (pinfunction "2_2") (pintype "passive"))
      (node (ref "C16") (pin "2") (pinfunction "2_2") (pintype "passive"))
      (node (ref "C17") (pin "2") (pinfunction "2_2") (pintype "passive"))
      (node (ref "C18") (pin "2") (pinfunction "2_2") (pintype "passive"))
      (node (ref "C19") (pin "2") (pinfunction "2_2") (pintype "passive"))
      (node (ref "C20") (pin "2") (pinfunction "2_2") (pintype "passive"))
      (node (ref "C21") (pin "2") (pinfunction "2_2") (pintype "passive"))
      (node (ref "C22") (pin "2") (pinfunction "2_2") (pintype "passive"))
      (node (ref "IC4") (pin "12") (pinfunction "PGND_1_12") (pintype "passive"))
      (node (ref "IC4") (pin "18") (pinfunction "PGND_2_18") (pintype "passive"))
      (node (ref "IC4") (pin "21") (pinfunction "EP_21") (pintype "passive"))
      (node (ref "IC4") (pin "9") (pinfunction "GND_9") (pintype "passive"))
      (node (ref "P1") (pin "1") (pinfunction "1_1") (pintype "passive"))
      (node (ref "P1") (pin "11") (pinfunction "11_11") (pintype "passive"))
      (node (ref "P1") (pin "13") (pinfunction "13_13") (pintype "passive"))
      (node (ref "P1") (pin "15") (pinfunction "15_15") (pintype "passive"))
      (node (ref "P1") (pin "17") (pinfunction "17_17") (pintype "passive"))
      (node (ref "P1") (pin "3") (pinfunction "3_3") (pintype "passive"))
      (node (ref "P1") (pin "5") (pinfunction "5_5") (pintype "passive"))
      (node (ref "P1") (pin "7") (pinfunction "7_7") (pintype "passive"))
      (node (ref "P1") (pin "9") (pinfunction "9_9") (pintype "passive"))
    )
    (net (code "32") (name "Net-(C5-Pad2)") (class "Default")
      (node (ref "C5") (pin "2") (pinfunction "2_2") (pintype "passive"))
      (node (ref "T1") (pin "8") (pinfunction "8_8") (pintype "passive"))
      (node (ref "T2") (pin "4") (pinfunction "4_4") (pintype "passive"))
    )
    (net (code "33") (name "Net-(D1-A1)") (class "Default")
      (node (ref "C7") (pin "1") (pinfunction "1_1") (pintype "passive"))
      (node (ref "D1") (pin "1") (pinfunction "A1_1") (pintype "passive"))
      (node (ref "R7") (pin "1") (pinfunction "A_1") (pintype "passive"))
      (node (ref "Z2") (pin "1") (pinfunction "A_1") (pintype "passive"))
    )
    (net (code "34") (name "Net-(D1-K2)") (class "Default")
      (node (ref "C6") (pin "1") (pinfunction "1_1") (pintype "passive"))
      (node (ref "D1") (pin "2") (pinfunction "K2_2") (pintype "passive"))
      (node (ref "R6") (pin "2") (pinfunction "2_2") (pintype "passive"))
      (node (ref "Z1") (pin "2") (pinfunction "K_2") (pintype "passive"))
    )
    (net (code "35") (name "Net-(IC1-+IN)") (class "Default")
      (node (ref "IC1") (pin "1") (pinfunction "+IN_1") (pintype "passive"))
      (node (ref "Voffset_in1") (pin "1") (pinfunction "Signal_1") (pintype "input"))
    )
    (net (code "36") (name "Net-(IC1--IN)") (class "Default")
      (node (ref "IC1") (pin "6") (pinfunction "OUT_6") (pintype "passive"))
      (node (ref "IC1") (pin "8") (pinfunction "-IN_8") (pintype "passive"))
      (node (ref "Voffset_out1") (pin "1") (pinfunction "Signal_1") (pintype "input"))
    )
    (net (code "37") (name "Net-(IC2-IN+)") (class "Default")
      (node (ref "IC2") (pin "3") (pinfunction "IN+_3") (pintype "input"))
      (node (ref "R3") (pin "1") (pinfunction "A_1") (pintype "passive"))
    )
    (net (code "38") (name "Net-(IC2-IN-)") (class "Default")
      (node (ref "IC2") (pin "2") (pinfunction "IN-_2") (pintype "input"))
      (node (ref "T1") (pin "9") (pinfunction "9_9") (pintype "passive"))
    )
    (net (code "39") (name "Net-(IC3-IN-)") (class "Default")
      (node (ref "C1") (pin "1") (pinfunction "1_1") (pintype "passive"))
      (node (ref "IC3") (pin "2") (pinfunction "IN-_2") (pintype "input"))
      (node (ref "T3") (pin "9") (pinfunction "9_9") (pintype "passive"))
    )
    (net (code "40") (name "Net-(R1-A)") (class "Default")
      (node (ref "R1") (pin "1") (pinfunction "A_1") (pintype "passive"))
      (node (ref "T3") (pin "3") (pinfunction "3_3") (pintype "passive"))
    )
    (net (code "41") (name "Net-(R1-Pad2)") (class "Default")
      (node (ref "R1") (pin "2") (pinfunction "2_2") (pintype "passive"))
      (node (ref "T3") (pin "10") (pinfunction "10_10") (pintype "passive"))
    )
    (net (code "42") (name "Net-(R10-A)") (class "Default")
      (node (ref "R10") (pin "1") (pinfunction "A_1") (pintype "passive"))
      (node (ref "T1") (pin "7") (pinfunction "7_7") (pintype "passive"))
    )
    (net (code "43") (name "Net-(R11-A)") (class "Default")
      (node (ref "R11") (pin "1") (pinfunction "A_1") (pintype "passive"))
      (node (ref "T1") (pin "6") (pinfunction "6_6") (pintype "passive"))
    )
    (net (code "44") (name "Net-(R12-A)") (class "Default")
      (node (ref "R12") (pin "1") (pinfunction "A_1") (pintype "passive"))
      (node (ref "T2") (pin "7") (pinfunction "7_7") (pintype "passive"))
    )
    (net (code "45") (name "Net-(R13-A)") (class "Default")
      (node (ref "R13") (pin "1") (pinfunction "A_1") (pintype "passive"))
      (node (ref "T2") (pin "6") (pinfunction "6_6") (pintype "passive"))
    )
    (net (code "46") (name "Net-(R14-A)") (class "Default")
      (node (ref "R14") (pin "1") (pinfunction "A_1") (pintype "passive"))
      (node (ref "T3") (pin "7") (pinfunction "7_7") (pintype "passive"))
    )
    (net (code "47") (name "Net-(R15-A)") (class "Default")
      (node (ref "R15") (pin "1") (pinfunction "A_1") (pintype "passive"))
      (node (ref "T3") (pin "6") (pinfunction "6_6") (pintype "passive"))
    )
    (net (code "48") (name "Net-(R17-A)") (class "Default")
      (node (ref "C8") (pin "2") (pinfunction "2_2") (pintype "passive"))
      (node (ref "R17") (pin "1") (pinfunction "A_1") (pintype "passive"))
      (node (ref "R8") (pin "1") (pinfunction "A_1") (pintype "passive"))
      (node (ref "R9") (pin "1") (pinfunction "A_1") (pintype "passive"))
    )
    (net (code "49") (name "Net-(RN1-Pad1)") (class "Default")
      (node (ref "RN1") (pin "1") (pinfunction "1_1") (pintype "passive"))
      (node (ref "RN1") (pin "2") (pinfunction "2_2") (pintype "passive"))
    )
    (net (code "50") (name "unconnected-(IC1-IC-Pad3)") (class "Default")
      (node (ref "IC1") (pin "3") (pinfunction "IC_3") (pintype "passive"))
    )
    (net (code "51") (name "unconnected-(IC2-SDCOM-Pad9)") (class "Default")
      (node (ref "IC2") (pin "9") (pinfunction "SDCOM_9") (pintype "input"))
    )
    (net (code "52") (name "unconnected-(IC2-~{SD}-Pad10)") (class "Default")
      (node (ref "IC2") (pin "10") (pinfunction "~{SD}_10") (pintype "input"))
    )
    (net (code "53") (name "unconnected-(IC3-SDCOM-Pad9)") (class "Default")
      (node (ref "IC3") (pin "9") (pinfunction "SDCOM_9") (pintype "input"))
    )
    (net (code "54") (name "unconnected-(IC3-~{SD}-Pad10)") (class "Default")
      (node (ref "IC3") (pin "10") (pinfunction "~{SD}_10") (pintype "input"))
    )
    (net (code "55") (name "unconnected-(IC4-OUT7-Pad11)") (class "Default")
      (node (ref "IC4") (pin "11") (pinfunction "OUT7_11") (pintype "passive"))
    )
    (net (code "56") (name "unconnected-(IC4-OUT8-Pad10)") (class "Default")
      (node (ref "IC4") (pin "10") (pinfunction "OUT8_10") (pintype "passive"))
    )
    (net (code "57") (name "unconnected-(P1-Pad4)") (class "Default")
      (node (ref "P1") (pin "4") (pinfunction "4_4") (pintype "passive"))
    )
    (net (code "58") (name "unconnected-(P1-Pad18)") (class "Default")
      (node (ref "P1") (pin "18") (pinfunction "18_18") (pintype "passive"))
    )
    (net (code "59") (name "unconnected-(P1-Pad19)") (class "Default")
      (node (ref "P1") (pin "19") (pinfunction "19_19") (pintype "passive"))
    )
    (net (code "60") (name "unconnected-(P1-Pad21)") (class "Default")
      (node (ref "P1") (pin "21") (pinfunction "21_21") (pintype "passive"))
    )
    (net (code "61") (name "unconnected-(P1-Pad30)") (class "Default")
      (node (ref "P1") (pin "30") (pinfunction "30_30") (pintype "passive"))
    )
    (net (code "62") (name "unconnected-(P2-Pad1)") (class "Default")
      (node (ref "P2") (pin "1") (pinfunction "1_1") (pintype "passive"))
    )
    (net (code "63") (name "unconnected-(P2-Pad2)") (class "Default")
      (node (ref "P2") (pin "2") (pinfunction "2_2") (pintype "passive"))
    )
    (net (code "64") (name "unconnected-(P2-Pad3)") (class "Default")
      (node (ref "P2") (pin "3") (pinfunction "3_3") (pintype "passive"))
    )
    (net (code "65") (name "unconnected-(P2-Pad4)") (class "Default")
      (node (ref "P2") (pin "4") (pinfunction "4_4") (pintype "passive"))
    )
    (net (code "66") (name "unconnected-(P2-Pad5)") (class "Default")
      (node (ref "P2") (pin "5") (pinfunction "5_5") (pintype "passive"))
    )
    (net (code "67") (name "unconnected-(P2-Pad6)") (class "Default")
      (node (ref "P2") (pin "6") (pinfunction "6_6") (pintype "passive"))
    )
    (net (code "68") (name "unconnected-(P2-Pad7)") (class "Default")
      (node (ref "P2") (pin "7") (pinfunction "7_7") (pintype "passive"))
    )
    (net (code "69") (name "unconnected-(P2-Pad8)") (class "Default")
      (node (ref "P2") (pin "8") (pinfunction "8_8") (pintype "passive"))
    )
    (net (code "70") (name "unconnected-(P2-Pad9)") (class "Default")
      (node (ref "P2") (pin "9") (pinfunction "9_9") (pintype "passive"))
    )
    (net (code "71") (name "unconnected-(P2-Pad10)") (class "Default")
      (node (ref "P2") (pin "10") (pinfunction "10_10") (pintype "passive"))
    )
    (net (code "72") (name "unconnected-(P2-Pad11)") (class "Default")
      (node (ref "P2") (pin "11") (pinfunction "11_11") (pintype "passive"))
    )
    (net (code "73") (name "unconnected-(P2-Pad12)") (class "Default")
      (node (ref "P2") (pin "12") (pinfunction "12_12") (pintype "passive"))
    )
    (net (code "74") (name "unconnected-(P2-Pad13)") (class "Default")
      (node (ref "P2") (pin "13") (pinfunction "13_13") (pintype "passive"))
    )
    (net (code "75") (name "unconnected-(P2-Pad14)") (class "Default")
      (node (ref "P2") (pin "14") (pinfunction "14_14") (pintype "passive"))
    )
    (net (code "76") (name "unconnected-(P2-Pad15)") (class "Default")
      (node (ref "P2") (pin "15") (pinfunction "15_15") (pintype "passive"))
    )
    (net (code "77") (name "unconnected-(P2-Pad16)") (class "Default")
      (node (ref "P2") (pin "16") (pinfunction "16_16") (pintype "passive"))
    )
    (net (code "78") (name "unconnected-(P2-Pad17)") (class "Default")
      (node (ref "P2") (pin "17") (pinfunction "17_17") (pintype "passive"))
    )
    (net (code "79") (name "unconnected-(P2-Pad18)") (class "Default")
      (node (ref "P2") (pin "18") (pinfunction "18_18") (pintype "passive"))
    )
    (net (code "80") (name "unconnected-(P2-Pad19)") (class "Default")
      (node (ref "P2") (pin "19") (pinfunction "19_19") (pintype "passive"))
    )
    (net (code "81") (name "unconnected-(P2-Pad20)") (class "Default")
      (node (ref "P2") (pin "20") (pinfunction "20_20") (pintype "passive"))
    )
    (net (code "82") (name "unconnected-(P2-Pad21)") (class "Default")
      (node (ref "P2") (pin "21") (pinfunction "21_21") (pintype "passive"))
    )
    (net (code "83") (name "unconnected-(P2-Pad22)") (class "Default")
      (node (ref "P2") (pin "22") (pinfunction "22_22") (pintype "passive"))
    )
    (net (code "84") (name "unconnected-(P2-Pad23)") (class "Default")
      (node (ref "P2") (pin "23") (pinfunction "23_23") (pintype "passive"))
    )
    (net (code "85") (name "unconnected-(P2-Pad24)") (class "Default")
      (node (ref "P2") (pin "24") (pinfunction "24_24") (pintype "passive"))
    )
    (net (code "86") (name "unconnected-(P2-Pad25)") (class "Default")
      (node (ref "P2") (pin "25") (pinfunction "25_25") (pintype "passive"))
    )
    (net (code "87") (name "unconnected-(P2-Pad26)") (class "Default")
      (node (ref "P2") (pin "26") (pinfunction "26_26") (pintype "passive"))
    )
    (net (code "88") (name "unconnected-(P2-Pad27)") (class "Default")
      (node (ref "P2") (pin "27") (pinfunction "27_27") (pintype "passive"))
    )
    (net (code "89") (name "unconnected-(P2-Pad28)") (class "Default")
      (node (ref "P2") (pin "28") (pinfunction "28_28") (pintype "passive"))
    )
    (net (code "90") (name "unconnected-(P2-Pad29)") (class "Default")
      (node (ref "P2") (pin "29") (pinfunction "29_29") (pintype "passive"))
    )
    (net (code "91") (name "unconnected-(P2-Pad30)") (class "Default")
      (node (ref "P2") (pin "30") (pinfunction "30_30") (pintype "passive"))
    )
    (net (code "92") (name "unconnected-(P2-Pad31)") (class "Default")
      (node (ref "P2") (pin "31") (pinfunction "31_31") (pintype "passive"))
    )
    (net (code "93") (name "unconnected-(P2-Pad32)") (class "Default")
      (node (ref "P2") (pin "32") (pinfunction "32_32") (pintype "passive"))
    )
    (net (code "94") (name "unconnected-(P2-Pad33)") (class "Default")
      (node (ref "P2") (pin "33") (pinfunction "33_33") (pintype "passive"))
    )
    (net (code "95") (name "unconnected-(P2-Pad34)") (class "Default")
      (node (ref "P2") (pin "34") (pinfunction "34_34") (pintype "passive"))
    )
    (net (code "96") (name "unconnected-(P2-Pad35)") (class "Default")
      (node (ref "P2") (pin "35") (pinfunction "35_35") (pintype "passive"))
    )
    (net (code "97") (name "unconnected-(P2-Pad36)") (class "Default")
      (node (ref "P2") (pin "36") (pinfunction "36_36") (pintype "passive"))
    )
  )
)
